# Sheet.net
KiCad netlist of a schematic drawn in Altium Designer
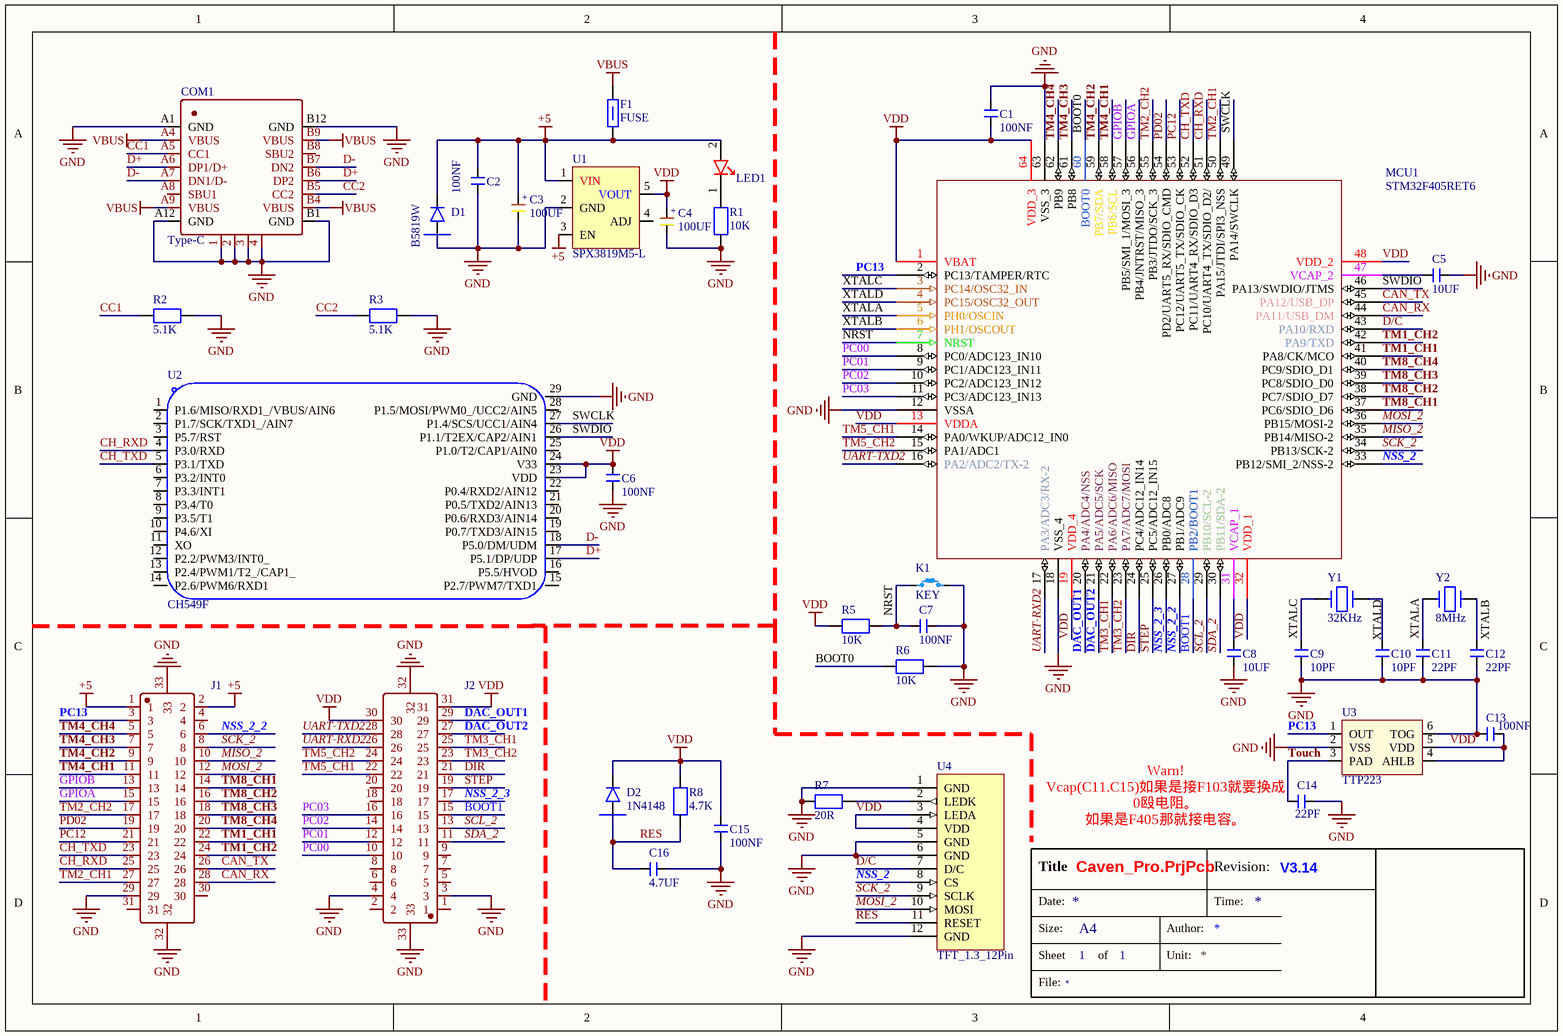
[diagram p0: Sheet.SchDoc]

(export (version "E")
  (design (tool "Eeschema 10.0.6"))
  (components
    (comp (ref "C1")
      (value "100NF")
      (footprint "CAP_0603")
      (description "CAP  12~50V")
      (libsource (lib "User") (part "CAP"))
    )
    (comp (ref "C2")
      (value "100NF")
      (footprint "CAP_0603")
      (description "CAP  12~50V")
      (libsource (lib "User") (part "CAP"))
    )
    (comp (ref "C3")
      (value "100UF")
      (footprint "CAP_3216_A")
      (description "CAP  6~12V  钽电容")
      (libsource (lib "User") (part "CAP_TA"))
    )
    (comp (ref "C4")
      (value "100UF")
      (footprint "CAP_3216_A")
      (description "CAP  6~12V  钽电容")
      (libsource (lib "User") (part "CAP_TA"))
    )
    (comp (ref "C5")
      (value "10UF")
      (footprint "CAP_0603")
      (description "CAP  12~50V")
      (libsource (lib "User") (part "CAP"))
    )
    (comp (ref "C6")
      (value "100NF")
      (footprint "CAP_0603")
      (description "CAP  12~50V")
      (libsource (lib "User") (part "CAP"))
    )
    (comp (ref "C7")
      (value "100NF")
      (footprint "CAP_0603")
      (description "CAP  12~50V")
      (libsource (lib "User") (part "CAP"))
    )
    (comp (ref "C8")
      (value "10UF")
      (footprint "CAP_0603")
      (description "CAP  12~50V")
      (libsource (lib "User") (part "CAP"))
    )
    (comp (ref "C9")
      (value "10PF")
      (footprint "CAP_0603")
      (description "CAP  12~50V")
      (libsource (lib "User") (part "CAP"))
    )
    (comp (ref "C10")
      (value "10PF")
      (footprint "CAP_0603")
      (description "CAP  12~50V")
      (libsource (lib "User") (part "CAP"))
    )
    (comp (ref "C11")
      (value "22PF")
      (footprint "CAP_0603")
      (description "CAP  12~50V")
      (libsource (lib "User") (part "CAP"))
    )
    (comp (ref "C12")
      (value "22PF")
      (footprint "CAP_0603")
      (description "CAP  12~50V")
      (libsource (lib "User") (part "CAP"))
    )
    (comp (ref "C13")
      (value "100NF")
      (footprint "CAP_0603")
      (description "CAP  12~50V")
      (libsource (lib "User") (part "CAP"))
    )
    (comp (ref "C14")
      (value "22PF")
      (footprint "CAP_0603")
      (description "CAP  12~50V")
      (libsource (lib "User") (part "CAP"))
    )
    (comp (ref "C15")
      (value "100NF")
      (footprint "CAP_0603")
      (description "CAP  12~50V")
      (libsource (lib "User") (part "CAP"))
    )
    (comp (ref "C16")
      (value "4.7UF")
      (footprint "CAP_0603")
      (description "CAP  12~50V")
      (libsource (lib "User") (part "CAP"))
    )
    (comp (ref "COM1")
      (value "Type-C")
      (footprint "USB-Type-C_16A")
      (description "USB")
      (libsource (lib "User") (part "USB-type_c"))
    )
    (comp (ref "D1")
      (value "B5819W")
      (footprint "DIODE_SOD123")
      (description "Diode_肖特基/二极管")
      (libsource (lib "User") (part "Diode-SM"))
    )
    (comp (ref "D2")
      (value "1N4148")
      (footprint "DIODE_SOD123")
      (description "Diode_肖特基/二极管")
      (libsource (lib "User") (part "Diode-SM"))
    )
    (comp (ref "F1") (value "FUSE") (footprint "Fuse_0603") (libsource (lib "User") (part "FUSE")))
    (comp (ref "J1")
      (value "31PIN")
      (footprint "BTB-DM3-31P")
      (description "BTB")
      (libsource (lib "User") (part "BTB_DF3_31Pin"))
    )
    (comp (ref "J2")
      (value "31PIN")
      (footprint "BTB-DM3-31P")
      (description "BTB")
      (libsource (lib "User") (part "BTB_DF3_31Pin"))
    )
    (comp (ref "K1")
      (value "KEY")
      (footprint "KEY_SMD")
      (description "Key")
      (libsource (lib "User") (part "KEY"))
    )
    (comp (ref "LED1")
      (value "LED_R/G/B/Y")
      (footprint "LED_0603_R")
      (description "LED")
      (libsource (lib "User") (part "LED_SMT"))
    )
    (comp (ref "MCU1")
      (value "STM32F405RET6")
      (footprint "LQFP_64_10X10")
      (description "MCU")
      (libsource (lib "User") (part "STM32f4_R"))
    )
    (comp (ref "R1")
      (value "10K")
      (footprint "RESC_0603_2")
      (description "RES 贴片")
      (libsource (lib "User") (part "RES_S"))
    )
    (comp (ref "R2")
      (value "5.1K")
      (footprint "RESC_0603_2")
      (description "RES 贴片")
      (libsource (lib "User") (part "RES"))
    )
    (comp (ref "R3")
      (value "5.1K")
      (footprint "RESC_0603_2")
      (description "RES 贴片")
      (libsource (lib "User") (part "RES"))
    )
    (comp (ref "R5")
      (value "10K")
      (footprint "RESC_0603_2")
      (description "RES 贴片")
      (libsource (lib "User") (part "RES_S"))
    )
    (comp (ref "R6")
      (value "10K")
      (footprint "RESC_0603_2")
      (description "RES 贴片")
      (libsource (lib "User") (part "RES_S"))
    )
    (comp (ref "R7")
      (value "20R")
      (footprint "RESC_0603_2")
      (description "RES 贴片")
      (libsource (lib "User") (part "RES_S"))
    )
    (comp (ref "R8")
      (value "4.7K")
      (footprint "RESC_0603_2")
      (description "RES 贴片")
      (libsource (lib "User") (part "RES_S"))
    )
    (comp (ref "U1")
      (value "SPX3819M5-L")
      (footprint "SOT23_5")
      (description "DC-DC   3.3V  500ma")
      (libsource (lib "User") (part "SPX3819M5-L"))
    )
    (comp (ref "U2")
      (value "CH549F")
      (footprint "QFN28_4X4_L")
      (description "MCU")
      (fields (field (name "MANUFACTURER") "WCH(南京沁恒)"))
      (libsource (lib "User") (part "CH549F"))
    )
    (comp (ref "U3")
      (value "TTP223")
      (footprint "SOT-23-6")
      (description "触摸芯片")
      (libsource (lib "User") (part "TTP223"))
    )
    (comp (ref "U4")
      (value "TFT_1.3_12Pin")
      (footprint "LCD_1.3B")
      (description "ST7789V-SPI")
      (libsource (lib "User") (part "LCD_1.3   T"))
    )
    (comp (ref "Y1")
      (value "32KHz")
      (footprint "XTAL_SMD_3215")
      (description "CRYSTAL")
      (libsource (lib "User") (part "XTAL"))
    )
    (comp (ref "Y2")
      (value "8MHz")
      (footprint "XTAL-SMD5032-2P")
      (description "CRYSTAL")
      (libsource (lib "User") (part "XTAL"))
    )
  )
  (nets
    (net (code "1") (name "+5") (class "Default")
      (node (ref "C2") (pin "2") (pinfunction "0_2") (pintype "passive"))
      (node (ref "C3") (pin "1") (pinfunction "0_1") (pintype "passive"))
      (node (ref "D1") (pin "2") (pinfunction "N_2") (pintype "passive"))
      (node (ref "F1") (pin "1") (pinfunction "1_1") (pintype "passive"))
      (node (ref "J1") (pin "1") (pinfunction "1_1") (pintype "passive"))
      (node (ref "J1") (pin "2") (pinfunction "2_2") (pintype "passive"))
      (node (ref "LED1") (pin "2") (pinfunction "+_2") (pintype "passive"))
      (node (ref "U1") (pin "1") (pinfunction "VIN_1") (pintype "passive"))
      (node (ref "U1") (pin "3") (pinfunction "EN_3") (pintype "passive"))
    )
    (net (code "2") (name "/BOOT0") (class "Default")
      (node (ref "MCU1") (pin "60") (pinfunction "BOOT0_60") (pintype "passive"))
      (node (ref "R6") (pin "1") (pinfunction "1_1") (pintype "passive"))
    )
    (net (code "3") (name "/BOOT1") (class "Default")
      (node (ref "J2") (pin "15") (pinfunction "15_15") (pintype "passive"))
      (node (ref "MCU1") (pin "28") (pinfunction "PB2/BOOT1_28") (pintype "passive"))
    )
    (net (code "4") (name "/CAN_RX") (class "Default")
      (node (ref "J1") (pin "28") (pinfunction "28_28") (pintype "passive"))
      (node (ref "MCU1") (pin "44") (pinfunction "PA11/USB_DM_44") (pintype "bidirectional"))
    )
    (net (code "5") (name "/CAN_TX") (class "Default")
      (node (ref "J1") (pin "26") (pinfunction "26_26") (pintype "passive"))
      (node (ref "MCU1") (pin "45") (pinfunction "PA12/USB_DP_45") (pintype "bidirectional"))
    )
    (net (code "6") (name "/CC1") (class "Default")
      (node (ref "COM1") (pin "A5") (pinfunction "CC1_A5") (pintype "passive"))
      (node (ref "R2") (pin "2") (pinfunction "2_2") (pintype "passive"))
    )
    (net (code "7") (name "/CC2") (class "Default")
      (node (ref "COM1") (pin "B5") (pinfunction "CC2_B5") (pintype "passive"))
      (node (ref "R3") (pin "2") (pinfunction "2_2") (pintype "passive"))
    )
    (net (code "8") (name "/CH_RXD") (class "Default")
      (node (ref "J1") (pin "25") (pinfunction "25_25") (pintype "passive"))
      (node (ref "MCU1") (pin "51") (pinfunction "PC10/UART4_TX/SDIO_D2/_51") (pintype "bidirectional"))
      (node (ref "U2") (pin "4") (pinfunction "P3.0/RXD_4") (pintype "passive"))
    )
    (net (code "9") (name "/CH_TXD") (class "Default")
      (node (ref "J1") (pin "23") (pinfunction "23_23") (pintype "passive"))
      (node (ref "MCU1") (pin "52") (pinfunction "PC11/UART4_RX/SDIO_D3_52") (pintype "bidirectional"))
      (node (ref "U2") (pin "5") (pinfunction "P3.1/TXD_5") (pintype "passive"))
    )
    (net (code "10") (name "/D+") (class "Default")
      (node (ref "COM1") (pin "A6") (pinfunction "DP1/D+_A6") (pintype "passive"))
      (node (ref "COM1") (pin "B6") (pinfunction "DP2_B6") (pintype "passive"))
      (node (ref "U2") (pin "17") (pinfunction "P5.1/DP/UDP_17") (pintype "passive"))
    )
    (net (code "11") (name "/D-") (class "Default")
      (node (ref "COM1") (pin "A7") (pinfunction "DN1/D-_A7") (pintype "passive"))
      (node (ref "COM1") (pin "B7") (pinfunction "DN2_B7") (pintype "passive"))
      (node (ref "U2") (pin "18") (pinfunction "P5.0/DM/UDM_18") (pintype "passive"))
    )
    (net (code "12") (name "/DAC_OUT1") (class "Default")
      (node (ref "J2") (pin "29") (pinfunction "29_29") (pintype "passive"))
      (node (ref "MCU1") (pin "20") (pinfunction "PA4/ADC4/NSS_20") (pintype "bidirectional"))
    )
    (net (code "13") (name "/DAC_OUT2") (class "Default")
      (node (ref "J2") (pin "27") (pinfunction "27_27") (pintype "passive"))
      (node (ref "MCU1") (pin "21") (pinfunction "PA5/ADC5/SCK_21") (pintype "bidirectional"))
    )
    (net (code "14") (name "/DIR") (class "Default")
      (node (ref "J2") (pin "21") (pinfunction "21_21") (pintype "passive"))
      (node (ref "MCU1") (pin "24") (pinfunction "PC4/ADC12_IN14_24") (pintype "bidirectional"))
    )
    (net (code "15") (name "/D{slash}C") (class "Default")
      (node (ref "MCU1") (pin "43") (pinfunction "PA10/RXD_43") (pintype "bidirectional"))
      (node (ref "U4") (pin "7") (pinfunction "D/C_7") (pintype "passive"))
    )
    (net (code "16") (name "/GPIOA") (class "Default")
      (node (ref "J1") (pin "15") (pinfunction "15_15") (pintype "passive"))
      (node (ref "MCU1") (pin "56") (pinfunction "PB4/JNTRST/MISO_3_56") (pintype "bidirectional"))
    )
    (net (code "17") (name "/GPIOB") (class "Default")
      (node (ref "J1") (pin "13") (pinfunction "13_13") (pintype "passive"))
      (node (ref "MCU1") (pin "57") (pinfunction "PB5/SMI_1/MOSI_3_57") (pintype "bidirectional"))
    )
    (net (code "18") (name "/MISO_2") (class "Default")
      (node (ref "J1") (pin "10") (pinfunction "10_10") (pintype "passive"))
      (node (ref "MCU1") (pin "35") (pinfunction "PB14/MISO-2_35") (pintype "bidirectional"))
    )
    (net (code "19") (name "/MOSI_2") (class "Default")
      (node (ref "J1") (pin "12") (pinfunction "12_12") (pintype "passive"))
      (node (ref "MCU1") (pin "36") (pinfunction "PB15/MOSI-2_36") (pintype "bidirectional"))
      (node (ref "U4") (pin "10") (pinfunction "MOSI_10") (pintype "input"))
    )
    (net (code "20") (name "/NRST") (class "Default")
      (node (ref "C7") (pin "2") (pinfunction "0_2") (pintype "passive"))
      (node (ref "K1") (pin "2") (pintype "passive"))
      (node (ref "MCU1") (pin "7") (pinfunction "NRST_7") (pintype "input"))
      (node (ref "R5") (pin "2") (pinfunction "2_2") (pintype "passive"))
    )
    (net (code "21") (name "/NSS_2") (class "Default")
      (node (ref "MCU1") (pin "33") (pinfunction "PB12/SMI_2/NSS-2_33") (pintype "bidirectional"))
      (node (ref "U4") (pin "8") (pinfunction "CS_8") (pintype "input"))
    )
    (net (code "22") (name "/NSS_2_2") (class "Default")
      (node (ref "J1") (pin "6") (pinfunction "6_6") (pintype "passive"))
      (node (ref "MCU1") (pin "27") (pinfunction "PB1/ADC9_27") (pintype "bidirectional"))
    )
    (net (code "23") (name "/NSS_2_3") (class "Default")
      (node (ref "J2") (pin "17") (pinfunction "17_17") (pintype "passive"))
      (node (ref "MCU1") (pin "26") (pinfunction "PB0/ADC8_26") (pintype "bidirectional"))
    )
    (net (code "24") (name "/PC00") (class "Default")
      (node (ref "J2") (pin "10") (pinfunction "10_10") (pintype "passive"))
      (node (ref "MCU1") (pin "8") (pinfunction "PC0/ADC123_IN10_8") (pintype "bidirectional"))
    )
    (net (code "25") (name "/PC01") (class "Default")
      (node (ref "J2") (pin "12") (pinfunction "12_12") (pintype "passive"))
      (node (ref "MCU1") (pin "9") (pinfunction "PC1/ADC123_IN11_9") (pintype "bidirectional"))
    )
    (net (code "26") (name "/PC02") (class "Default")
      (node (ref "J2") (pin "14") (pinfunction "14_14") (pintype "passive"))
      (node (ref "MCU1") (pin "10") (pinfunction "PC2/ADC123_IN12_10") (pintype "bidirectional"))
    )
    (net (code "27") (name "/PC03") (class "Default")
      (node (ref "J2") (pin "16") (pinfunction "16_16") (pintype "passive"))
      (node (ref "MCU1") (pin "11") (pinfunction "PC3/ADC123_IN13_11") (pintype "bidirectional"))
    )
    (net (code "28") (name "/PC12") (class "Default")
      (node (ref "J1") (pin "21") (pinfunction "21_21") (pintype "passive"))
      (node (ref "MCU1") (pin "53") (pinfunction "PC12/UART5_TX/SDIO_CK_53") (pintype "bidirectional"))
    )
    (net (code "29") (name "/PC13") (class "Default")
      (node (ref "J1") (pin "3") (pinfunction "3_3") (pintype "passive"))
      (node (ref "MCU1") (pin "2") (pinfunction "PC13/TAMPER/RTC_2") (pintype "bidirectional"))
      (node (ref "U3") (pin "1") (pinfunction "OUT_1") (pintype "passive"))
    )
    (net (code "30") (name "/PD02") (class "Default")
      (node (ref "J1") (pin "19") (pinfunction "19_19") (pintype "passive"))
      (node (ref "MCU1") (pin "54") (pinfunction "PD2/UART5_RX/SDIO_CMD_54") (pintype "bidirectional"))
    )
    (net (code "31") (name "/RES") (class "Default")
      (node (ref "C16") (pin "1") (pinfunction "0_1") (pintype "passive"))
      (node (ref "D2") (pin "1") (pinfunction "P_1") (pintype "passive"))
      (node (ref "R8") (pin "2") (pinfunction "2_2") (pintype "passive"))
      (node (ref "U4") (pin "11") (pinfunction "RESET_11") (pintype "passive"))
    )
    (net (code "32") (name "/SCK_2") (class "Default")
      (node (ref "J1") (pin "8") (pinfunction "8_8") (pintype "passive"))
      (node (ref "MCU1") (pin "34") (pinfunction "PB13/SCK-2_34") (pintype "bidirectional"))
      (node (ref "U4") (pin "9") (pinfunction "SCLK_9") (pintype "input"))
    )
    (net (code "33") (name "/SCL_2") (class "Default")
      (node (ref "J2") (pin "13") (pinfunction "13_13") (pintype "passive"))
      (node (ref "MCU1") (pin "29") (pinfunction "PB10/SCL-2_29") (pintype "bidirectional"))
    )
    (net (code "34") (name "/SDA_2") (class "Default")
      (node (ref "J2") (pin "11") (pinfunction "11_11") (pintype "passive"))
      (node (ref "MCU1") (pin "30") (pinfunction "PB11/SDA-2_30") (pintype "bidirectional"))
    )
    (net (code "35") (name "/STEP") (class "Default")
      (node (ref "J2") (pin "19") (pinfunction "19_19") (pintype "passive"))
      (node (ref "MCU1") (pin "25") (pinfunction "PC5/ADC12_IN15_25") (pintype "bidirectional"))
    )
    (net (code "36") (name "/SWCLK") (class "Default")
      (node (ref "MCU1") (pin "49") (pinfunction "PA14/SWCLK_49") (pintype "bidirectional"))
      (node (ref "U2") (pin "27") (pinfunction "P1.4/SCS/UCC1/AIN4_27") (pintype "passive"))
    )
    (net (code "37") (name "/SWDIO") (class "Default")
      (node (ref "MCU1") (pin "46") (pinfunction "PA13/SWDIO/JTMS_46") (pintype "bidirectional"))
      (node (ref "U2") (pin "26") (pinfunction "P1.1/T2EX/CAP2/AIN1_26") (pintype "passive"))
    )
    (net (code "38") (name "/TM1_CH1") (class "Default")
      (node (ref "J1") (pin "22") (pinfunction "22_22") (pintype "passive"))
      (node (ref "MCU1") (pin "41") (pinfunction "PA8/CK/MCO_41") (pintype "bidirectional"))
    )
    (net (code "39") (name "/TM1_CH2") (class "Default")
      (node (ref "J1") (pin "24") (pinfunction "24_24") (pintype "passive"))
      (node (ref "MCU1") (pin "42") (pinfunction "PA9/TXD_42") (pintype "bidirectional"))
    )
    (net (code "40") (name "/TM2_CH1") (class "Default")
      (node (ref "J1") (pin "27") (pinfunction "27_27") (pintype "passive"))
      (node (ref "MCU1") (pin "50") (pinfunction "PA15/JTDI/SPI3_NSS_50") (pintype "bidirectional"))
    )
    (net (code "41") (name "/TM2_CH2") (class "Default")
      (node (ref "J1") (pin "17") (pinfunction "17_17") (pintype "passive"))
      (node (ref "MCU1") (pin "55") (pinfunction "PB3/JTDO/SCK_3_55") (pintype "bidirectional"))
    )
    (net (code "42") (name "/TM3_CH1") (class "Default")
      (node (ref "J2") (pin "25") (pinfunction "25_25") (pintype "passive"))
      (node (ref "MCU1") (pin "22") (pinfunction "PA6/ADC6/MISO_22") (pintype "bidirectional"))
    )
    (net (code "43") (name "/TM3_CH2") (class "Default")
      (node (ref "J2") (pin "23") (pinfunction "23_23") (pintype "passive"))
      (node (ref "MCU1") (pin "23") (pinfunction "PA7/ADC7/MOSI_23") (pintype "bidirectional"))
    )
    (net (code "44") (name "/TM4_CH1") (class "Default")
      (node (ref "J1") (pin "11") (pinfunction "11_11") (pintype "passive"))
      (node (ref "MCU1") (pin "58") (pinfunction "PB6/SCL_58") (pintype "bidirectional"))
    )
    (net (code "45") (name "/TM4_CH2") (class "Default")
      (node (ref "J1") (pin "9") (pinfunction "9_9") (pintype "passive"))
      (node (ref "MCU1") (pin "59") (pinfunction "PB7/SDA_59") (pintype "bidirectional"))
    )
    (net (code "46") (name "/TM4_CH3") (class "Default")
      (node (ref "J1") (pin "7") (pinfunction "7_7") (pintype "passive"))
      (node (ref "MCU1") (pin "61") (pinfunction "PB8_61") (pintype "bidirectional"))
    )
    (net (code "47") (name "/TM4_CH4") (class "Default")
      (node (ref "J1") (pin "5") (pinfunction "5_5") (pintype "passive"))
      (node (ref "MCU1") (pin "62") (pinfunction "PB9_62") (pintype "bidirectional"))
    )
    (net (code "48") (name "/TM5_CH1") (class "Default")
      (node (ref "J2") (pin "22") (pinfunction "22_22") (pintype "passive"))
      (node (ref "MCU1") (pin "14") (pinfunction "PA0/WKUP/ADC12_IN0_14") (pintype "bidirectional"))
    )
    (net (code "49") (name "/TM5_CH2") (class "Default")
      (node (ref "J2") (pin "24") (pinfunction "24_24") (pintype "passive"))
      (node (ref "MCU1") (pin "15") (pinfunction "PA1/ADC1_15") (pintype "bidirectional"))
    )
    (net (code "50") (name "/TM8_CH1") (class "Default")
      (node (ref "J1") (pin "14") (pinfunction "14_14") (pintype "passive"))
      (node (ref "MCU1") (pin "37") (pinfunction "PC6/SDIO_D6_37") (pintype "bidirectional"))
    )
    (net (code "51") (name "/TM8_CH2") (class "Default")
      (node (ref "J1") (pin "16") (pinfunction "16_16") (pintype "passive"))
      (node (ref "MCU1") (pin "38") (pinfunction "PC7/SDIO_D7_38") (pintype "bidirectional"))
    )
    (net (code "52") (name "/TM8_CH3") (class "Default")
      (node (ref "J1") (pin "18") (pinfunction "18_18") (pintype "passive"))
      (node (ref "MCU1") (pin "39") (pinfunction "PC8/SDIO_D0_39") (pintype "bidirectional"))
    )
    (net (code "53") (name "/TM8_CH4") (class "Default")
      (node (ref "J1") (pin "20") (pinfunction "20_20") (pintype "passive"))
      (node (ref "MCU1") (pin "40") (pinfunction "PC9/SDIO_D1_40") (pintype "bidirectional"))
    )
    (net (code "54") (name "/Touch") (class "Default")
      (node (ref "C14") (pin "1") (pinfunction "0_1") (pintype "passive"))
      (node (ref "U3") (pin "3") (pinfunction "PAD_3") (pintype "passive"))
    )
    (net (code "55") (name "/UART-RXD2") (class "Default")
      (node (ref "J2") (pin "26") (pinfunction "26_26") (pintype "passive"))
      (node (ref "MCU1") (pin "17") (pinfunction "PA3/ADC3/RX-2_17") (pintype "bidirectional"))
    )
    (net (code "56") (name "/UART-TXD2") (class "Default")
      (node (ref "J2") (pin "28") (pinfunction "28_28") (pintype "passive"))
      (node (ref "MCU1") (pin "16") (pinfunction "PA2/ADC2/TX-2_16") (pintype "bidirectional"))
    )
    (net (code "57") (name "/XTALA") (class "Default")
      (node (ref "C11") (pin "1") (pinfunction "0_1") (pintype "passive"))
      (node (ref "MCU1") (pin "5") (pinfunction "PH0/OSCIN_5") (pintype "input"))
      (node (ref "Y2") (pin "2") (pinfunction "2_2") (pintype "passive"))
    )
    (net (code "58") (name "/XTALB") (class "Default")
      (node (ref "C12") (pin "1") (pinfunction "0_1") (pintype "passive"))
      (node (ref "MCU1") (pin "6") (pinfunction "PH1/OSCOUT_6") (pintype "input"))
      (node (ref "Y2") (pin "1") (pinfunction "1_1") (pintype "passive"))
    )
    (net (code "59") (name "/XTALC") (class "Default")
      (node (ref "C9") (pin "1") (pinfunction "0_1") (pintype "passive"))
      (node (ref "MCU1") (pin "3") (pinfunction "PC14/OSC32_IN_3") (pintype "input"))
      (node (ref "Y1") (pin "2") (pinfunction "2_2") (pintype "passive"))
    )
    (net (code "60") (name "/XTALD") (class "Default")
      (node (ref "C10") (pin "1") (pinfunction "0_1") (pintype "passive"))
      (node (ref "MCU1") (pin "4") (pinfunction "PC15/OSC32_OUT_4") (pintype "input"))
      (node (ref "Y1") (pin "1") (pinfunction "1_1") (pintype "passive"))
    )
    (net (code "61") (name "GND") (class "Default")
      (node (ref "C1") (pin "1") (pinfunction "0_1") (pintype "passive"))
      (node (ref "C10") (pin "2") (pinfunction "0_2") (pintype "passive"))
      (node (ref "C11") (pin "2") (pinfunction "0_2") (pintype "passive"))
      (node (ref "C12") (pin "2") (pinfunction "0_2") (pintype "passive"))
      (node (ref "C13") (pin "1") (pinfunction "0_1") (pintype "passive"))
      (node (ref "C14") (pin "2") (pinfunction "0_2") (pintype "passive"))
      (node (ref "C15") (pin "2") (pinfunction "0_2") (pintype "passive"))
      (node (ref "C16") (pin "2") (pinfunction "0_2") (pintype "passive"))
      (node (ref "C2") (pin "1") (pinfunction "0_1") (pintype "passive"))
      (node (ref "C3") (pin "2") (pinfunction "0_2") (pintype "passive"))
      (node (ref "C4") (pin "2") (pinfunction "0_2") (pintype "passive"))
      (node (ref "C5") (pin "1") (pinfunction "0_1") (pintype "passive"))
      (node (ref "C6") (pin "1") (pinfunction "0_1") (pintype "passive"))
      (node (ref "C7") (pin "1") (pinfunction "0_1") (pintype "passive"))
      (node (ref "C8") (pin "1") (pinfunction "0_1") (pintype "passive"))
      (node (ref "C9") (pin "2") (pinfunction "0_2") (pintype "passive"))
      (node (ref "COM1") (pin "1") (pinfunction "1_1") (pintype "passive"))
      (node (ref "COM1") (pin "2") (pinfunction "2_2") (pintype "passive"))
      (node (ref "COM1") (pin "3") (pinfunction "3_3") (pintype "passive"))
      (node (ref "COM1") (pin "4") (pinfunction "4_4") (pintype "passive"))
      (node (ref "COM1") (pin "A1") (pinfunction "GND_A1") (pintype "passive"))
      (node (ref "COM1") (pin "A12") (pinfunction "GND_A12") (pintype "passive"))
      (node (ref "COM1") (pin "B1") (pinfunction "GND_B1") (pintype "passive"))
      (node (ref "COM1") (pin "B12") (pinfunction "GND_B12") (pintype "passive"))
      (node (ref "D1") (pin "1") (pinfunction "P_1") (pintype "passive"))
      (node (ref "J1") (pin "29") (pinfunction "29_29") (pintype "passive"))
      (node (ref "J1") (pin "32") (pinfunction "32_32") (pintype "passive"))
      (node (ref "J1") (pin "33") (pinfunction "33_33") (pintype "passive"))
      (node (ref "J2") (pin "3") (pinfunction "3_3") (pintype "passive"))
      (node (ref "J2") (pin "32") (pinfunction "32_32") (pintype "passive"))
      (node (ref "J2") (pin "33") (pinfunction "33_33") (pintype "passive"))
      (node (ref "J2") (pin "4") (pinfunction "4_4") (pintype "passive"))
      (node (ref "K1") (pin "1") (pintype "passive"))
      (node (ref "MCU1") (pin "12") (pinfunction "VSSA_12") (pintype "power_in"))
      (node (ref "MCU1") (pin "18") (pinfunction "VSS_4_18") (pintype "power_in"))
      (node (ref "MCU1") (pin "63") (pinfunction "VSS_3_63") (pintype "power_in"))
      (node (ref "R1") (pin "1") (pinfunction "1_1") (pintype "passive"))
      (node (ref "R2") (pin "1") (pinfunction "1_1") (pintype "passive"))
      (node (ref "R3") (pin "1") (pinfunction "1_1") (pintype "passive"))
      (node (ref "R6") (pin "2") (pinfunction "2_2") (pintype "passive"))
      (node (ref "R7") (pin "1") (pinfunction "1_1") (pintype "passive"))
      (node (ref "U1") (pin "2") (pinfunction "GND_2") (pintype "passive"))
      (node (ref "U2") (pin "29") (pinfunction "GND_29") (pintype "passive"))
      (node (ref "U3") (pin "2") (pinfunction "VSS_2") (pintype "passive"))
      (node (ref "U3") (pin "6") (pinfunction "TOG_6") (pintype "passive"))
      (node (ref "U4") (pin "1") (pinfunction "GND_1") (pintype "passive"))
      (node (ref "U4") (pin "12") (pinfunction "GND_12") (pintype "passive"))
      (node (ref "U4") (pin "5") (pinfunction "GND_5") (pintype "passive"))
      (node (ref "U4") (pin "6") (pinfunction "GND_6") (pintype "passive"))
    )
    (net (code "62") (name "Net-(LED1--)") (class "Default")
      (node (ref "LED1") (pin "1") (pinfunction "-_1") (pintype "passive"))
      (node (ref "R1") (pin "2") (pinfunction "2_2") (pintype "passive"))
    )
    (net (code "63") (name "Net-(MCU1-VCAP_1)") (class "Default")
      (node (ref "C8") (pin "2") (pinfunction "0_2") (pintype "passive"))
      (node (ref "MCU1") (pin "31") (pinfunction "VCAP_1_31") (pintype "passive"))
    )
    (net (code "64") (name "Net-(MCU1-VCAP_2)") (class "Default")
      (node (ref "C5") (pin "2") (pinfunction "0_2") (pintype "passive"))
      (node (ref "MCU1") (pin "47") (pinfunction "VCAP_2_47") (pintype "passive"))
    )
    (net (code "65") (name "Net-(U4-LEDK)") (class "Default")
      (node (ref "R7") (pin "2") (pinfunction "2_2") (pintype "passive"))
      (node (ref "U4") (pin "2") (pinfunction "LEDK_2") (pintype "output"))
    )
    (net (code "66") (name "VBUS") (class "Default")
      (node (ref "COM1") (pin "A4") (pinfunction "VBUS_A4") (pintype "passive"))
      (node (ref "COM1") (pin "A9") (pinfunction "VBUS_A9") (pintype "passive"))
      (node (ref "COM1") (pin "B4") (pinfunction "VBUS_B4") (pintype "passive"))
      (node (ref "COM1") (pin "B9") (pinfunction "VBUS_B9") (pintype "passive"))
      (node (ref "F1") (pin "2") (pinfunction "2_2") (pintype "passive"))
    )
    (net (code "67") (name "VDD") (class "Default")
      (node (ref "C1") (pin "2") (pinfunction "0_2") (pintype "passive"))
      (node (ref "C13") (pin "2") (pinfunction "0_2") (pintype "passive"))
      (node (ref "C15") (pin "1") (pinfunction "0_1") (pintype "passive"))
      (node (ref "C4") (pin "1") (pinfunction "0_1") (pintype "passive"))
      (node (ref "C6") (pin "2") (pinfunction "0_2") (pintype "passive"))
      (node (ref "D2") (pin "2") (pinfunction "N_2") (pintype "passive"))
      (node (ref "J2") (pin "30") (pinfunction "30_30") (pintype "passive"))
      (node (ref "J2") (pin "31") (pinfunction "31_31") (pintype "passive"))
      (node (ref "MCU1") (pin "1") (pinfunction "VBAT_1") (pintype "power_in"))
      (node (ref "MCU1") (pin "13") (pinfunction "VDDA_13") (pintype "power_in"))
      (node (ref "MCU1") (pin "19") (pinfunction "VDD_4_19") (pintype "power_in"))
      (node (ref "MCU1") (pin "32") (pinfunction "VDD_1_32") (pintype "power_in"))
      (node (ref "MCU1") (pin "48") (pinfunction "VDD_2_48") (pintype "power_in"))
      (node (ref "MCU1") (pin "64") (pinfunction "VDD_3_64") (pintype "power_in"))
      (node (ref "R5") (pin "1") (pinfunction "1_1") (pintype "passive"))
      (node (ref "R8") (pin "1") (pinfunction "1_1") (pintype "passive"))
      (node (ref "U1") (pin "5") (pinfunction "VOUT_5") (pintype "passive"))
      (node (ref "U2") (pin "23") (pinfunction "VDD_23") (pintype "passive"))
      (node (ref "U2") (pin "24") (pinfunction "V33_24") (pintype "passive"))
      (node (ref "U3") (pin "4") (pinfunction "AHLB_4") (pintype "passive"))
      (node (ref "U3") (pin "5") (pinfunction "VDD_5") (pintype "passive"))
      (node (ref "U4") (pin "3") (pinfunction "LEDA_3") (pintype "input"))
      (node (ref "U4") (pin "4") (pinfunction "VDD_4") (pintype "passive"))
    )
    (net (code "68") (name "unconnected-(COM1-SBU1-PadA8)") (class "Default")
      (node (ref "COM1") (pin "A8") (pinfunction "SBU1_A8") (pintype "passive"))
    )
    (net (code "69") (name "unconnected-(COM1-SBU2-PadB8)") (class "Default")
      (node (ref "COM1") (pin "B8") (pinfunction "SBU2_B8") (pintype "passive"))
    )
    (net (code "70") (name "unconnected-(J1-Pad4)") (class "Default")
      (node (ref "J1") (pin "4") (pinfunction "4_4") (pintype "passive"))
    )
    (net (code "71") (name "unconnected-(J1-Pad30)") (class "Default")
      (node (ref "J1") (pin "30") (pinfunction "30_30") (pintype "passive"))
    )
    (net (code "72") (name "unconnected-(J1-Pad31)") (class "Default")
      (node (ref "J1") (pin "31") (pinfunction "31_31") (pintype "passive"))
    )
    (net (code "73") (name "unconnected-(J2-Pad1)") (class "Default")
      (node (ref "J2") (pin "1") (pinfunction "1_1") (pintype "passive"))
    )
    (net (code "74") (name "unconnected-(J2-Pad2)") (class "Default")
      (node (ref "J2") (pin "2") (pinfunction "2_2") (pintype "passive"))
    )
    (net (code "75") (name "unconnected-(J2-Pad5)") (class "Default")
      (node (ref "J2") (pin "5") (pinfunction "5_5") (pintype "passive"))
    )
    (net (code "76") (name "unconnected-(J2-Pad6)") (class "Default")
      (node (ref "J2") (pin "6") (pinfunction "6_6") (pintype "passive"))
    )
    (net (code "77") (name "unconnected-(J2-Pad7)") (class "Default")
      (node (ref "J2") (pin "7") (pinfunction "7_7") (pintype "passive"))
    )
    (net (code "78") (name "unconnected-(J2-Pad8)") (class "Default")
      (node (ref "J2") (pin "8") (pinfunction "8_8") (pintype "passive"))
    )
    (net (code "79") (name "unconnected-(J2-Pad9)") (class "Default")
      (node (ref "J2") (pin "9") (pinfunction "9_9") (pintype "passive"))
    )
    (net (code "80") (name "unconnected-(J2-Pad18)") (class "Default")
      (node (ref "J2") (pin "18") (pinfunction "18_18") (pintype "passive"))
    )
    (net (code "81") (name "unconnected-(J2-Pad20)") (class "Default")
      (node (ref "J2") (pin "20") (pinfunction "20_20") (pintype "passive"))
    )
    (net (code "82") (name "unconnected-(U1-ADJ-Pad4)") (class "Default")
      (node (ref "U1") (pin "4") (pinfunction "ADJ_4") (pintype "passive"))
    )
    (net (code "83") (name "unconnected-(U2-P0.4{slash}RXD2{slash}AIN12-Pad22)") (class "Default")
      (node (ref "U2") (pin "22") (pinfunction "P0.4/RXD2/AIN12_22") (pintype "passive"))
    )
    (net (code "84") (name "unconnected-(U2-P0.5{slash}TXD2{slash}AIN13-Pad21)") (class "Default")
      (node (ref "U2") (pin "21") (pinfunction "P0.5/TXD2/AIN13_21") (pintype "passive"))
    )
    (net (code "85") (name "unconnected-(U2-P0.6{slash}RXD3{slash}AIN14-Pad20)") (class "Default")
      (node (ref "U2") (pin "20") (pinfunction "P0.6/RXD3/AIN14_20") (pintype "passive"))
    )
    (net (code "86") (name "unconnected-(U2-P0.7{slash}TXD3{slash}AIN15-Pad19)") (class "Default")
      (node (ref "U2") (pin "19") (pinfunction "P0.7/TXD3/AIN15_19") (pintype "passive"))
    )
    (net (code "87") (name "unconnected-(U2-P1.0{slash}T2{slash}CAP1{slash}AIN0-Pad25)") (class "Default")
      (node (ref "U2") (pin "25") (pinfunction "P1.0/T2/CAP1/AIN0_25") (pintype "passive"))
    )
    (net (code "88") (name "unconnected-(U2-P1.5{slash}MOSI{slash}PWM0_{slash}UCC2{slash}AIN5-Pad28)") (class "Default")
      (node (ref "U2") (pin "28") (pinfunction "P1.5/MOSI/PWM0_/UCC2/AIN5_28") (pintype "passive"))
    )
    (net (code "89") (name "unconnected-(U2-P1.6{slash}MISO{slash}RXD1_{slash}VBUS{slash}AIN6-Pad1)") (class "Default")
      (node (ref "U2") (pin "1") (pinfunction "P1.6/MISO/RXD1_/VBUS/AIN6_1") (pintype "passive"))
    )
    (net (code "90") (name "unconnected-(U2-P1.7{slash}SCK{slash}TXD1_{slash}AIN7-Pad2)") (class "Default")
      (node (ref "U2") (pin "2") (pinfunction "P1.7/SCK/TXD1_/AIN7_2") (pintype "passive"))
    )
    (net (code "91") (name "unconnected-(U2-P2.2{slash}PWM3{slash}INT0_-Pad12)") (class "Default")
      (node (ref "U2") (pin "12") (pinfunction "P2.2/PWM3/INT0__12") (pintype "passive"))
    )
    (net (code "92") (name "unconnected-(U2-P2.4{slash}PWM1{slash}T2_{slash}CAP1_-Pad13)") (class "Default")
      (node (ref "U2") (pin "13") (pinfunction "P2.4/PWM1/T2_/CAP1__13") (pintype "passive"))
    )
    (net (code "93") (name "unconnected-(U2-P2.6{slash}PWM6{slash}RXD1-Pad14)") (class "Default")
      (node (ref "U2") (pin "14") (pinfunction "P2.6/PWM6/RXD1_14") (pintype "passive"))
    )
    (net (code "94") (name "unconnected-(U2-P2.7{slash}PWM7{slash}TXD1-Pad15)") (class "Default")
      (node (ref "U2") (pin "15") (pinfunction "P2.7/PWM7/TXD1_15") (pintype "passive"))
    )
    (net (code "95") (name "unconnected-(U2-P3.2{slash}INT0-Pad6)") (class "Default")
      (node (ref "U2") (pin "6") (pinfunction "P3.2/INT0_6") (pintype "passive"))
    )
    (net (code "96") (name "unconnected-(U2-P3.3{slash}INT1-Pad7)") (class "Default")
      (node (ref "U2") (pin "7") (pinfunction "P3.3/INT1_7") (pintype "passive"))
    )
    (net (code "97") (name "unconnected-(U2-P3.4{slash}T0-Pad8)") (class "Default")
      (node (ref "U2") (pin "8") (pinfunction "P3.4/T0_8") (pintype "passive"))
    )
    (net (code "98") (name "unconnected-(U2-P3.5{slash}T1-Pad9)") (class "Default")
      (node (ref "U2") (pin "9") (pinfunction "P3.5/T1_9") (pintype "passive"))
    )
    (net (code "99") (name "unconnected-(U2-P4.6{slash}XI-Pad10)") (class "Default")
      (node (ref "U2") (pin "10") (pinfunction "P4.6/XI_10") (pintype "passive"))
    )
    (net (code "100") (name "unconnected-(U2-P5.5{slash}HVOD-Pad16)") (class "Default")
      (node (ref "U2") (pin "16") (pinfunction "P5.5/HVOD_16") (pintype "passive"))
    )
    (net (code "101") (name "unconnected-(U2-P5.7{slash}RST-Pad3)") (class "Default")
      (node (ref "U2") (pin "3") (pinfunction "P5.7/RST_3") (pintype "passive"))
    )
    (net (code "102") (name "unconnected-(U2-XO-Pad11)") (class "Default")
      (node (ref "U2") (pin "11") (pinfunction "XO_11") (pintype "passive"))
    )
  )
)
